# ProProject_Board4_2024-06-03.net
KiCad netlist of a schematic drawn in EasyEDA Pro
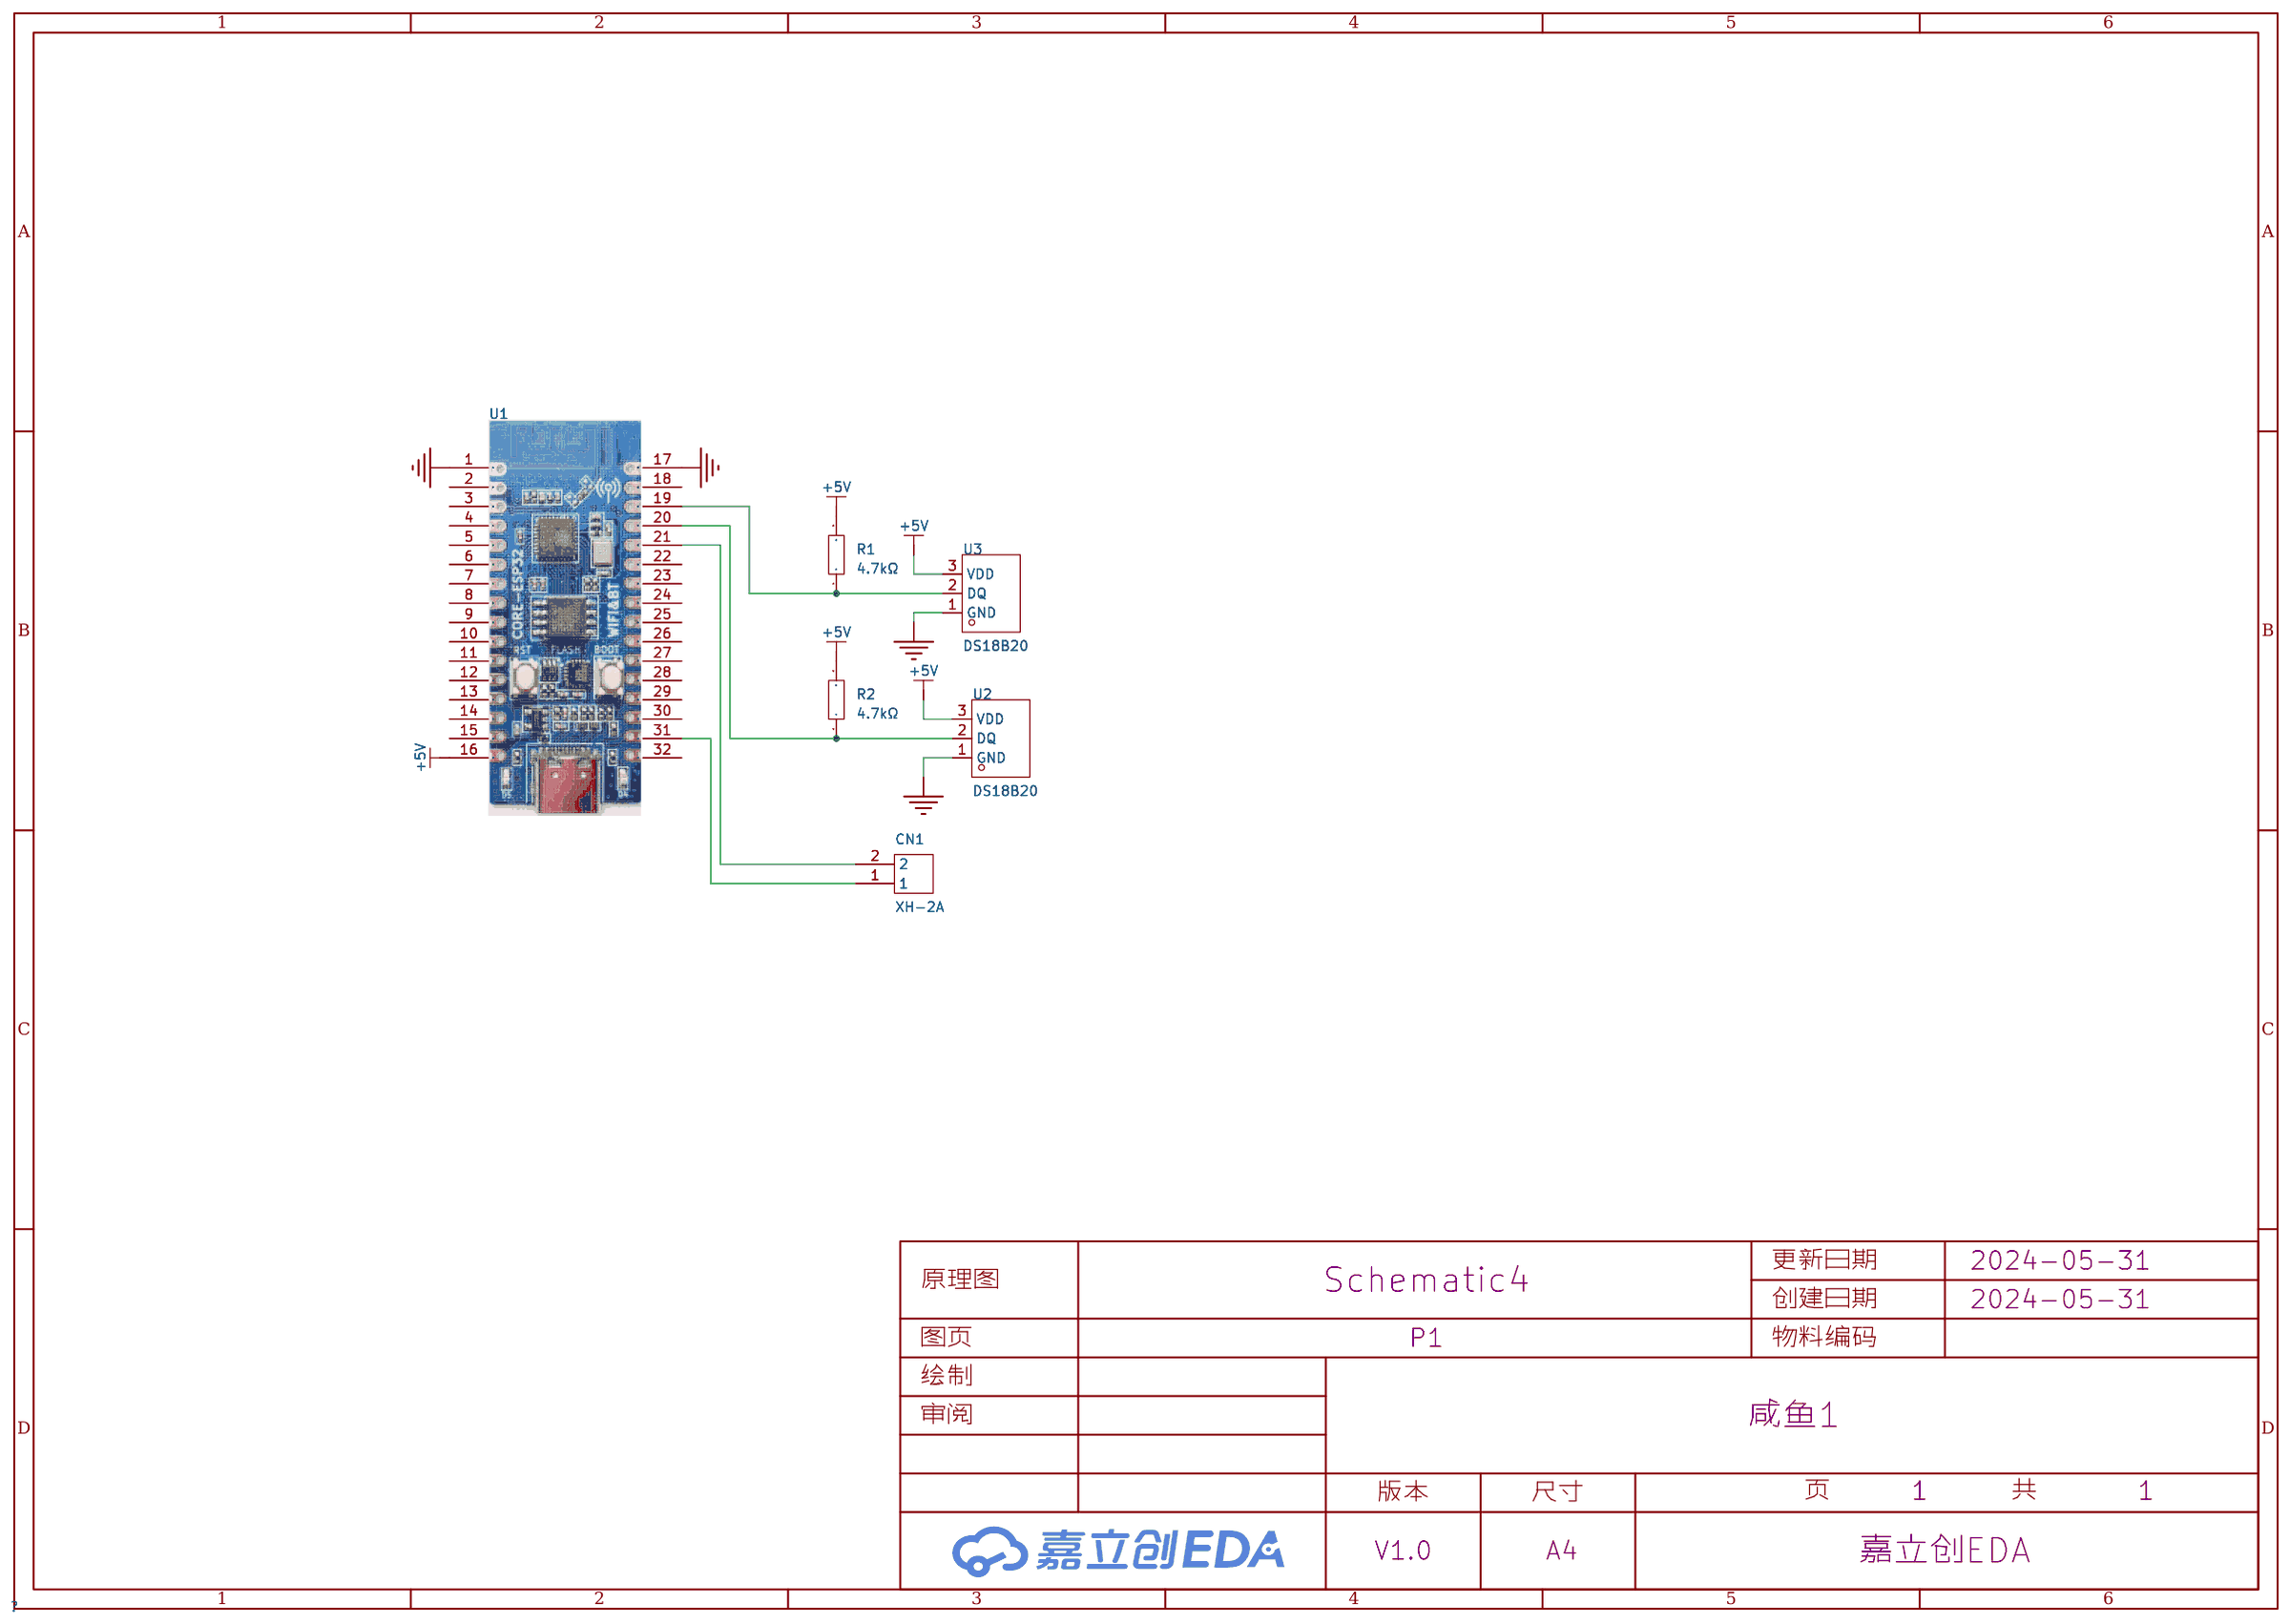
[diagram p0: schematic sheet]

(export (version "E")
  (design (tool "Eeschema 10.0.6"))
  (components
    (comp (ref "CN1")
      (value "XH-2A")
      (footprint "easyedapro:CONN-TH_XH-2A")
      (description "插针结构:1x2P;间距:2.5mm;安装方式:-;参考系列:XH;总PIN数:2P;排数:1;每排PIN数:2;行距:-;触头材质:-;")
      (fields (field (name "Manufacturer") "BOOMELE(博穆精密)"))
      (libsource (lib "easyedapro") (part "XH-2A"))
    )
    (comp (ref "R1")
      (value "4.7kΩ")
      (footprint "easyedapro:R0805")
      (description "电阻类型:厚膜电阻;阻值:4.7kΩ;精度:±1%;功率:125mW;最大工作电压:150V;温度系数:±100ppm/°C;")
      (fields
        (field (name "Manufacturer Part") "0805W8F4701T5E")
        (field (name "Manufacturer") "UNI-ROYAL(厚声)")
      )
      (libsource (lib "easyedapro") (part "0805W8F4701T5E"))
    )
    (comp (ref "R2")
      (value "4.7kΩ")
      (footprint "easyedapro:R0805")
      (description "电阻类型:厚膜电阻;阻值:4.7kΩ;精度:±1%;功率:125mW;最大工作电压:150V;温度系数:±100ppm/°C;")
      (fields
        (field (name "Manufacturer Part") "0805W8F4701T5E")
        (field (name "Manufacturer") "UNI-ROYAL(厚声)")
      )
      (libsource (lib "easyedapro") (part "0805W8F4701T5E"))
    )
    (comp (ref "U1")
      (value "~")
      (footprint "easyedapro:ESP32C3-CORE开发板")
      (libsource (lib "easyedapro") (part "ESP32C3-CORE开发板"))
    )
    (comp (ref "U2")
      (value "DS18B20")
      (footprint "easyedapro:TO-92-3_L4.9-W3.7-P1.27-L")
      (description "温度范围:-55°C~+125°C;精度:±0.4°C;接口类型:-;")
      (fields (field (name "Manufacturer") "UMW(友台半导体)"))
      (libsource (lib "easyedapro") (part "DS18B20"))
    )
    (comp (ref "U3")
      (value "DS18B20")
      (footprint "easyedapro:TO-92-3_L4.9-W3.7-P1.27-L")
      (description "温度范围:-55°C~+125°C;精度:±0.4°C;接口类型:-;")
      (fields (field (name "Manufacturer") "UMW(友台半导体)"))
      (libsource (lib "easyedapro") (part "DS18B20"))
    )
  )
  (nets
    (net (code "1") (name "+5V") (class "Default")
      (node (ref "R1") (pin "2") (pinfunction "2_2") (pintype "input"))
      (node (ref "R2") (pin "2") (pinfunction "2_2") (pintype "input"))
      (node (ref "U1") (pin "16") (pinfunction "16_16") (pintype "input"))
      (node (ref "U2") (pin "3") (pinfunction "VDD_3") (pintype "unspecified"))
      (node (ref "U3") (pin "3") (pinfunction "VDD_3") (pintype "unspecified"))
    )
    (net (code "2") (name "GND") (class "Default")
      (node (ref "U1") (pin "1") (pinfunction "1_1") (pintype "input"))
      (node (ref "U1") (pin "17") (pinfunction "17_17") (pintype "input"))
      (node (ref "U2") (pin "1") (pinfunction "GND_1") (pintype "unspecified"))
      (node (ref "U3") (pin "1") (pinfunction "GND_1") (pintype "unspecified"))
    )
    (net (code "3") (name "Net-(CN1-Pad1)") (class "Default")
      (node (ref "CN1") (pin "1") (pinfunction "1_1") (pintype "unspecified"))
      (node (ref "U1") (pin "31") (pinfunction "31_31") (pintype "input"))
    )
    (net (code "4") (name "Net-(CN1-Pad2)") (class "Default")
      (node (ref "CN1") (pin "2") (pinfunction "2_2") (pintype "unspecified"))
      (node (ref "U1") (pin "21") (pinfunction "21_21") (pintype "input"))
    )
    (net (code "5") (name "Net-(U2-DQ)") (class "Default")
      (node (ref "R2") (pin "1") (pinfunction "1_1") (pintype "input"))
      (node (ref "U1") (pin "20") (pinfunction "20_20") (pintype "input"))
      (node (ref "U2") (pin "2") (pinfunction "DQ_2") (pintype "unspecified"))
    )
    (net (code "6") (name "Net-(U3-DQ)") (class "Default")
      (node (ref "R1") (pin "1") (pinfunction "1_1") (pintype "input"))
      (node (ref "U1") (pin "19") (pinfunction "19_19") (pintype "input"))
      (node (ref "U3") (pin "2") (pinfunction "DQ_2") (pintype "unspecified"))
    )
    (net (code "7") (name "unconnected-(U1-Pad2)") (class "Default")
      (node (ref "U1") (pin "2") (pinfunction "2_2") (pintype "input"))
    )
    (net (code "8") (name "unconnected-(U1-Pad3)") (class "Default")
      (node (ref "U1") (pin "3") (pinfunction "3_3") (pintype "input"))
    )
    (net (code "9") (name "unconnected-(U1-Pad4)") (class "Default")
      (node (ref "U1") (pin "4") (pinfunction "4_4") (pintype "input"))
    )
    (net (code "10") (name "unconnected-(U1-Pad5)") (class "Default")
      (node (ref "U1") (pin "5") (pinfunction "5_5") (pintype "input"))
    )
    (net (code "11") (name "unconnected-(U1-Pad6)") (class "Default")
      (node (ref "U1") (pin "6") (pinfunction "6_6") (pintype "input"))
    )
    (net (code "12") (name "unconnected-(U1-Pad7)") (class "Default")
      (node (ref "U1") (pin "7") (pinfunction "7_7") (pintype "input"))
    )
    (net (code "13") (name "unconnected-(U1-Pad8)") (class "Default")
      (node (ref "U1") (pin "8") (pinfunction "8_8") (pintype "input"))
    )
    (net (code "14") (name "unconnected-(U1-Pad9)") (class "Default")
      (node (ref "U1") (pin "9") (pinfunction "9_9") (pintype "input"))
    )
    (net (code "15") (name "unconnected-(U1-Pad10)") (class "Default")
      (node (ref "U1") (pin "10") (pinfunction "10_10") (pintype "input"))
    )
    (net (code "16") (name "unconnected-(U1-Pad11)") (class "Default")
      (node (ref "U1") (pin "11") (pinfunction "11_11") (pintype "input"))
    )
    (net (code "17") (name "unconnected-(U1-Pad12)") (class "Default")
      (node (ref "U1") (pin "12") (pinfunction "12_12") (pintype "input"))
    )
    (net (code "18") (name "unconnected-(U1-Pad13)") (class "Default")
      (node (ref "U1") (pin "13") (pinfunction "13_13") (pintype "input"))
    )
    (net (code "19") (name "unconnected-(U1-Pad14)") (class "Default")
      (node (ref "U1") (pin "14") (pinfunction "14_14") (pintype "input"))
    )
    (net (code "20") (name "unconnected-(U1-Pad15)") (class "Default")
      (node (ref "U1") (pin "15") (pinfunction "15_15") (pintype "input"))
    )
    (net (code "21") (name "unconnected-(U1-Pad18)") (class "Default")
      (node (ref "U1") (pin "18") (pinfunction "18_18") (pintype "input"))
    )
    (net (code "22") (name "unconnected-(U1-Pad22)") (class "Default")
      (node (ref "U1") (pin "22") (pinfunction "22_22") (pintype "input"))
    )
    (net (code "23") (name "unconnected-(U1-Pad23)") (class "Default")
      (node (ref "U1") (pin "23") (pinfunction "23_23") (pintype "input"))
    )
    (net (code "24") (name "unconnected-(U1-Pad24)") (class "Default")
      (node (ref "U1") (pin "24") (pinfunction "24_24") (pintype "input"))
    )
    (net (code "25") (name "unconnected-(U1-Pad25)") (class "Default")
      (node (ref "U1") (pin "25") (pinfunction "25_25") (pintype "input"))
    )
    (net (code "26") (name "unconnected-(U1-Pad26)") (class "Default")
      (node (ref "U1") (pin "26") (pinfunction "26_26") (pintype "input"))
    )
    (net (code "27") (name "unconnected-(U1-Pad27)") (class "Default")
      (node (ref "U1") (pin "27") (pinfunction "27_27") (pintype "input"))
    )
    (net (code "28") (name "unconnected-(U1-Pad28)") (class "Default")
      (node (ref "U1") (pin "28") (pinfunction "28_28") (pintype "input"))
    )
    (net (code "29") (name "unconnected-(U1-Pad29)") (class "Default")
      (node (ref "U1") (pin "29") (pinfunction "29_29") (pintype "input"))
    )
    (net (code "30") (name "unconnected-(U1-Pad30)") (class "Default")
      (node (ref "U1") (pin "30") (pinfunction "30_30") (pintype "input"))
    )
    (net (code "31") (name "unconnected-(U1-Pad32)") (class "Default")
      (node (ref "U1") (pin "32") (pinfunction "32_32") (pintype "input"))
    )
  )
)
